# BRD9057A_SiWx917M_4-Layer_ExtSw_REF_DES_.net
KiCad netlist of a schematic drawn in Altium Designer
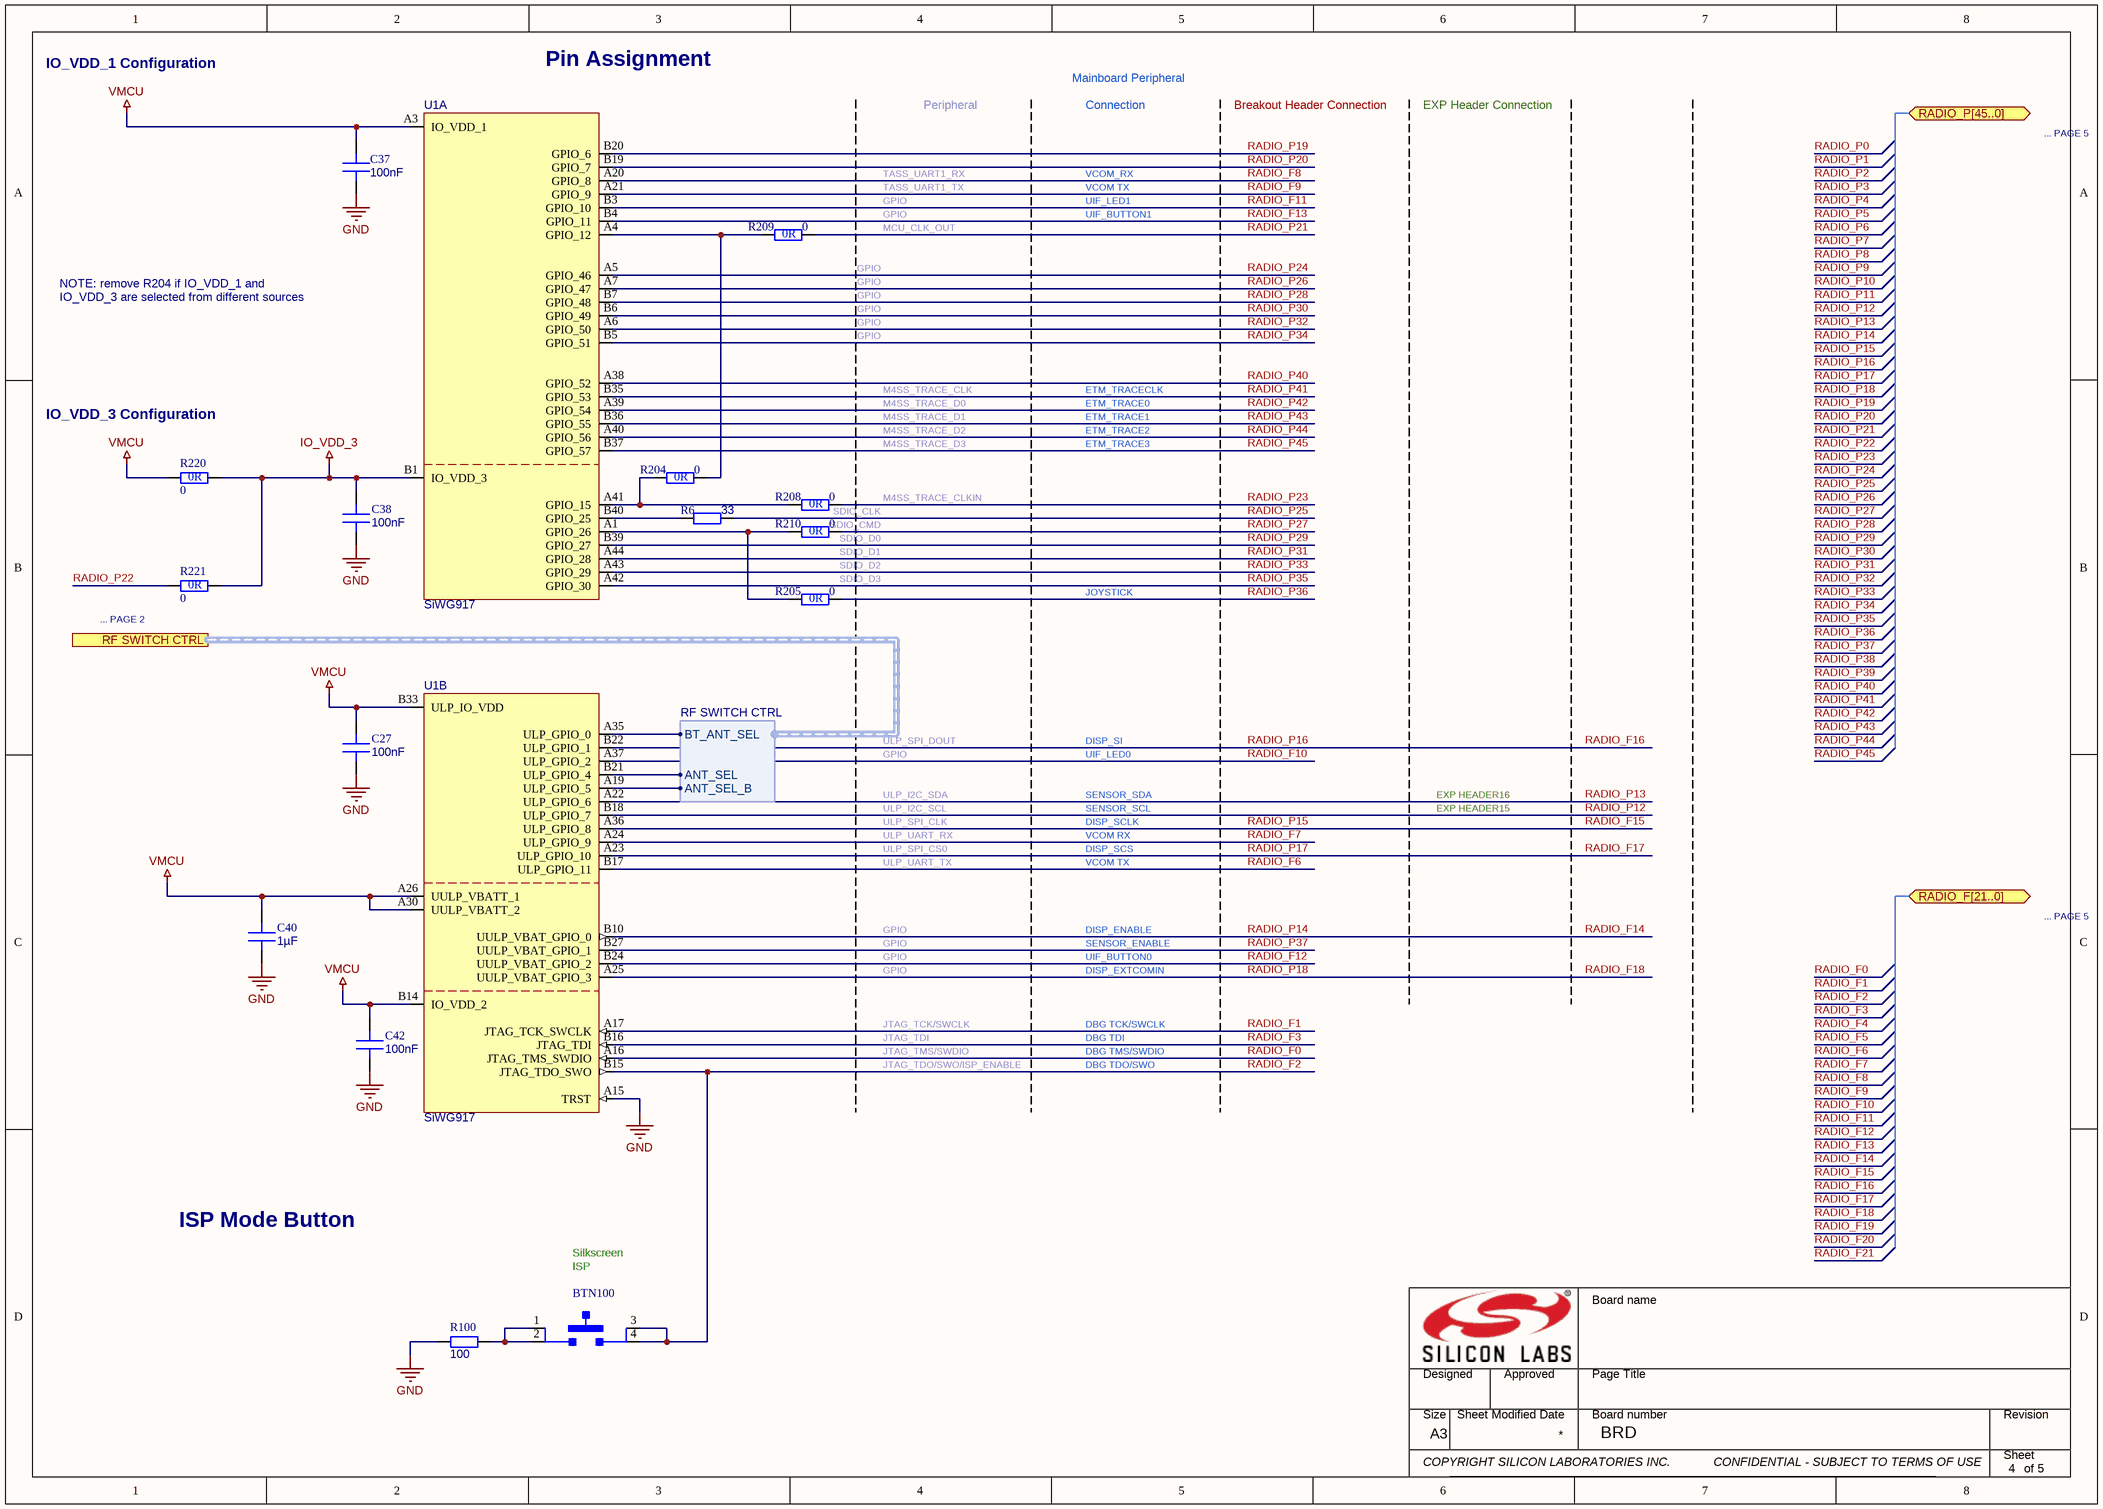
[diagram p0: BRD9057A_SiWx917M_4-Layer_ExtSw_REF_DES_A01_Page_4.SchDoc]

(export (version "E")
  (design (tool "Eeschema 10.0.6"))
  (components
    (comp (ref "BTN100")
      (value "PTS810 SJM 250 SMTR LFS")
      (footprint "SW_PTS810SJM250SMTRLFS")
      (description "Tactile Switch SPST-NO 0.05A 16V")
      (fields (field (name "MANUFACTURER") "C&K"))
      (libsource (lib "SiLabs Production Server") (part "SW_TACTILE_SPST_4PIN"))
    )
    (comp (ref "C27")
      (value "100nF")
      (footprint "C0201_GM")
      (description "CAP CER 0201 X5R 100nF 16V 10%")
      (fields (field (name "TOLERANCE") "10%"))
      (libsource (lib "SiLabs Production Server") (part "Capacitor"))
    )
    (comp (ref "C37")
      (value "100nF")
      (footprint "C0201_GM")
      (description "CAP CER 0201 X5R 100nF 16V 10%")
      (fields (field (name "TOLERANCE") "10%"))
      (libsource (lib "SiLabs Production Server") (part "Capacitor"))
    )
    (comp (ref "C38")
      (value "100nF")
      (footprint "C0201_GM")
      (description "CAP CER 0201 X5R 100nF 16V 10%")
      (fields (field (name "TOLERANCE") "10%"))
      (libsource (lib "SiLabs Production Server") (part "Capacitor"))
    )
    (comp (ref "C40")
      (value "1µF")
      (footprint "C0201_GM")
      (description "CAP CER 0201 X5R 1uF 16V 20%")
      (fields (field (name "TOLERANCE") "20%"))
      (libsource (lib "SiLabs Production Server") (part "Capacitor"))
    )
    (comp (ref "C42")
      (value "100nF")
      (footprint "C0201_GM")
      (description "CAP CER 0201 X5R 100nF 16V 10%")
      (fields (field (name "TOLERANCE") "10%"))
      (libsource (lib "SiLabs Production Server") (part "Capacitor"))
    )
    (comp (ref "R6")
      (value "33")
      (footprint "R0201")
      (description "RES 0201 33R 1/20W 1% 200ppm")
      (fields (field (name "TOLERANCE") "1%"))
      (libsource (lib "SiLabs Production Server") (part "Resistor"))
    )
    (comp (ref "R100")
      (value "100")
      (footprint "R0201")
      (description "RES 0201 100R 1/20W 1% 200ppm")
      (fields (field (name "TOLERANCE") "1%"))
      (libsource (lib "SiLabs Production Server") (part "Resistor"))
    )
    (comp (ref "R204")
      (value "0")
      (footprint "R0402")
      (description "RES 0402 0R")
      (fields (field (name "TOLERANCE") "0%"))
      (libsource (lib "SiLabs Production Server") (part "Resistor-Jumper"))
    )
    (comp (ref "R205")
      (value "0")
      (footprint "R0402")
      (description "RES 0402 0R")
      (fields (field (name "TOLERANCE") "0%"))
      (libsource (lib "SiLabs Production Server") (part "Resistor-Jumper"))
    )
    (comp (ref "R208")
      (value "0")
      (footprint "R0402")
      (description "RES 0402 0R")
      (fields (field (name "TOLERANCE") "0%"))
      (libsource (lib "SiLabs Production Server") (part "Resistor-Jumper"))
    )
    (comp (ref "R209")
      (value "0")
      (footprint "R0402")
      (description "RES 0402 0R")
      (fields (field (name "TOLERANCE") "0%"))
      (libsource (lib "SiLabs Production Server") (part "Resistor-Jumper"))
    )
    (comp (ref "R210")
      (value "0")
      (footprint "R0402")
      (description "RES 0402 0R")
      (fields (field (name "TOLERANCE") "0%"))
      (libsource (lib "SiLabs Production Server") (part "Resistor-Jumper"))
    )
    (comp (ref "R220")
      (value "0")
      (footprint "R0402")
      (description "RES 0402 0R")
      (fields (field (name "TOLERANCE") "0%"))
      (libsource (lib "SiLabs Production Server") (part "Resistor-Jumper"))
    )
    (comp (ref "R221")
      (value "0")
      (footprint "R0402")
      (description "RES 0402 0R")
      (fields (field (name "TOLERANCE") "0%"))
      (libsource (lib "SiLabs Production Server") (part "Resistor-Jumper"))
    )
    (comp (ref "U1")
      (value "SiWG917")
      (footprint "QFN84_SI_SiWx917_A1")
      (description "IC SoC 32BIT 8MB FLASH QFN84 2.4GHz Single Band Wi-Fi")
      (fields (field (name "MANUFACTURER") "Silicon Labs") (field (name "VOLTAGE") "3.63V"))
      (libsource (lib "SiLabs Production Server") (part "SiWx917"))
    )
  )
  (nets
    (net (code "4") (name "/ANT_SEL") (class "Default")
      (node (ref "U1") (pin "B21") (pinfunction "ULP_GPIO_4_B21") (pintype "bidirectional"))
    )
    (net (code "5") (name "/ANT_SEL_B") (class "Default")
      (node (ref "U1") (pin "A19") (pinfunction "ULP_GPIO_5_A19") (pintype "bidirectional"))
    )
    (net (code "6") (name "/BT_ANT_SEL") (class "Default")
      (node (ref "U1") (pin "A35") (pinfunction "ULP_GPIO_0_A35") (pintype "bidirectional"))
    )
    (net (code "7") (name "/RADIO_F0") (class "Default")
      (node (ref "U1") (pin "A16") (pinfunction "JTAG_TMS_SWDIO_A16") (pintype "input"))
    )
    (net (code "8") (name "/RADIO_F1") (class "Default")
      (node (ref "U1") (pin "A17") (pinfunction "JTAG_TCK_SWCLK_A17") (pintype "input"))
    )
    (net (code "9") (name "/RADIO_F2") (class "Default")
      (node (ref "BTN100") (pin "3") (pinfunction "3_3") (pintype "passive"))
      (node (ref "BTN100") (pin "4") (pinfunction "4_4") (pintype "passive"))
      (node (ref "U1") (pin "B15") (pinfunction "JTAG_TDO_SWO_B15") (pintype "output"))
    )
    (net (code "10") (name "/RADIO_F3") (class "Default")
      (node (ref "U1") (pin "B16") (pinfunction "JTAG_TDI_B16") (pintype "input"))
    )
    (net (code "13") (name "/RADIO_F6") (class "Default")
      (node (ref "U1") (pin "B17") (pinfunction "ULP_GPIO_11_B17") (pintype "bidirectional"))
    )
    (net (code "14") (name "/RADIO_F7") (class "Default")
      (node (ref "U1") (pin "A24") (pinfunction "ULP_GPIO_9_A24") (pintype "bidirectional"))
    )
    (net (code "15") (name "/RADIO_F8") (class "Default")
      (node (ref "U1") (pin "A20") (pinfunction "GPIO_8_A20") (pintype "bidirectional"))
    )
    (net (code "16") (name "/RADIO_F9") (class "Default")
      (node (ref "U1") (pin "A21") (pinfunction "GPIO_9_A21") (pintype "bidirectional"))
    )
    (net (code "17") (name "/RADIO_F10") (class "Default")
      (node (ref "U1") (pin "A37") (pinfunction "ULP_GPIO_2_A37") (pintype "bidirectional"))
    )
    (net (code "18") (name "/RADIO_F11") (class "Default")
      (node (ref "U1") (pin "B3") (pinfunction "GPIO_10_B3") (pintype "bidirectional"))
    )
    (net (code "19") (name "/RADIO_F12") (class "Default")
      (node (ref "U1") (pin "B24") (pinfunction "UULP_VBAT_GPIO_2_B24") (pintype "bidirectional"))
    )
    (net (code "20") (name "/RADIO_F13") (class "Default")
      (node (ref "U1") (pin "B4") (pinfunction "GPIO_11_B4") (pintype "bidirectional"))
    )
    (net (code "37") (name "/RADIO_P12") (class "Default")
      (node (ref "U1") (pin "B18") (pinfunction "ULP_GPIO_7_B18") (pintype "bidirectional"))
    )
    (net (code "38") (name "/RADIO_P13") (class "Default")
      (node (ref "U1") (pin "A22") (pinfunction "ULP_GPIO_6_A22") (pintype "bidirectional"))
    )
    (net (code "39") (name "/RADIO_P14") (class "Default")
      (node (ref "U1") (pin "B10") (pinfunction "UULP_VBAT_GPIO_0_B10") (pintype "output"))
    )
    (net (code "40") (name "/RADIO_P15") (class "Default")
      (node (ref "U1") (pin "A36") (pinfunction "ULP_GPIO_8_A36") (pintype "bidirectional"))
    )
    (net (code "41") (name "/RADIO_P16") (class "Default")
      (node (ref "U1") (pin "B22") (pinfunction "ULP_GPIO_1_B22") (pintype "bidirectional"))
    )
    (net (code "42") (name "/RADIO_P17") (class "Default")
      (node (ref "U1") (pin "A23") (pinfunction "ULP_GPIO_10_A23") (pintype "bidirectional"))
    )
    (net (code "43") (name "/RADIO_P18") (class "Default")
      (node (ref "U1") (pin "A25") (pinfunction "UULP_VBAT_GPIO_3_A25") (pintype "bidirectional"))
    )
    (net (code "44") (name "/RADIO_P19") (class "Default")
      (node (ref "U1") (pin "B20") (pinfunction "GPIO_6_B20") (pintype "bidirectional"))
    )
    (net (code "45") (name "/RADIO_P20") (class "Default")
      (node (ref "U1") (pin "B19") (pinfunction "GPIO_7_B19") (pintype "bidirectional"))
    )
    (net (code "46") (name "/RADIO_P21") (class "Default")
      (node (ref "R209") (pin "2") (pinfunction "2_2") (pintype "passive"))
    )
    (net (code "47") (name "/RADIO_P22") (class "Default")
      (node (ref "R221") (pin "1") (pinfunction "1_1") (pintype "passive"))
    )
    (net (code "48") (name "/RADIO_P23") (class "Default")
      (node (ref "R208") (pin "2") (pinfunction "2_2") (pintype "passive"))
    )
    (net (code "49") (name "/RADIO_P24") (class "Default")
      (node (ref "U1") (pin "A5") (pinfunction "GPIO_46_A5") (pintype "bidirectional"))
    )
    (net (code "50") (name "/RADIO_P25") (class "Default")
      (node (ref "R6") (pin "2") (pinfunction "2_2") (pintype "passive"))
    )
    (net (code "51") (name "/RADIO_P26") (class "Default")
      (node (ref "U1") (pin "A7") (pinfunction "GPIO_47_A7") (pintype "bidirectional"))
    )
    (net (code "52") (name "/RADIO_P27") (class "Default")
      (node (ref "R210") (pin "2") (pinfunction "2_2") (pintype "passive"))
    )
    (net (code "53") (name "/RADIO_P28") (class "Default")
      (node (ref "U1") (pin "B7") (pinfunction "GPIO_48_B7") (pintype "bidirectional"))
    )
    (net (code "54") (name "/RADIO_P29") (class "Default")
      (node (ref "U1") (pin "B39") (pinfunction "GPIO_27_B39") (pintype "bidirectional"))
    )
    (net (code "55") (name "/RADIO_P30") (class "Default")
      (node (ref "U1") (pin "B6") (pinfunction "GPIO_49_B6") (pintype "bidirectional"))
    )
    (net (code "56") (name "/RADIO_P31") (class "Default")
      (node (ref "U1") (pin "A44") (pinfunction "GPIO_28_A44") (pintype "bidirectional"))
    )
    (net (code "57") (name "/RADIO_P32") (class "Default")
      (node (ref "U1") (pin "A6") (pinfunction "GPIO_50_A6") (pintype "bidirectional"))
    )
    (net (code "58") (name "/RADIO_P33") (class "Default")
      (node (ref "U1") (pin "A43") (pinfunction "GPIO_29_A43") (pintype "bidirectional"))
    )
    (net (code "59") (name "/RADIO_P34") (class "Default")
      (node (ref "U1") (pin "B5") (pinfunction "GPIO_51_B5") (pintype "bidirectional"))
    )
    (net (code "60") (name "/RADIO_P35") (class "Default")
      (node (ref "U1") (pin "A42") (pinfunction "GPIO_30_A42") (pintype "bidirectional"))
    )
    (net (code "61") (name "/RADIO_P36") (class "Default")
      (node (ref "R205") (pin "2") (pinfunction "2_2") (pintype "passive"))
    )
    (net (code "62") (name "/RADIO_P37") (class "Default")
      (node (ref "U1") (pin "B27") (pinfunction "UULP_VBAT_GPIO_1_B27") (pintype "bidirectional"))
    )
    (net (code "65") (name "/RADIO_P40") (class "Default")
      (node (ref "U1") (pin "A38") (pinfunction "GPIO_52_A38") (pintype "bidirectional"))
    )
    (net (code "66") (name "/RADIO_P41") (class "Default")
      (node (ref "U1") (pin "B35") (pinfunction "GPIO_53_B35") (pintype "bidirectional"))
    )
    (net (code "67") (name "/RADIO_P42") (class "Default")
      (node (ref "U1") (pin "A39") (pinfunction "GPIO_54_A39") (pintype "bidirectional"))
    )
    (net (code "68") (name "/RADIO_P43") (class "Default")
      (node (ref "U1") (pin "B36") (pinfunction "GPIO_55_B36") (pintype "bidirectional"))
    )
    (net (code "69") (name "/RADIO_P44") (class "Default")
      (node (ref "U1") (pin "A40") (pinfunction "GPIO_56_A40") (pintype "bidirectional"))
    )
    (net (code "70") (name "/RADIO_P45") (class "Default")
      (node (ref "U1") (pin "B37") (pinfunction "GPIO_57_B37") (pintype "bidirectional"))
    )
    (net (code "73") (name "GND") (class "Default")
      (node (ref "C27") (pin "1") (pinfunction "1_1") (pintype "passive"))
      (node (ref "C37") (pin "1") (pinfunction "1_1") (pintype "passive"))
      (node (ref "C38") (pin "1") (pinfunction "1_1") (pintype "passive"))
      (node (ref "C40") (pin "1") (pinfunction "1_1") (pintype "passive"))
      (node (ref "C42") (pin "1") (pinfunction "1_1") (pintype "passive"))
      (node (ref "R100") (pin "2") (pinfunction "2_2") (pintype "passive"))
      (node (ref "U1") (pin "A15") (pinfunction "TRST_A15") (pintype "input"))
    )
    (net (code "74") (name "IO_VDD_3") (class "Default")
      (node (ref "C38") (pin "2") (pinfunction "2_2") (pintype "passive"))
      (node (ref "R220") (pin "2") (pinfunction "2_2") (pintype "passive"))
      (node (ref "R221") (pin "2") (pinfunction "2_2") (pintype "passive"))
      (node (ref "U1") (pin "B1") (pinfunction "IO_VDD_3_B1") (pintype "power_in"))
    )
    (net (code "75") (name "Net-(BTN100-Pad1)") (class "Default")
      (node (ref "BTN100") (pin "1") (pinfunction "1_1") (pintype "passive"))
      (node (ref "BTN100") (pin "2") (pinfunction "2_2") (pintype "passive"))
      (node (ref "R100") (pin "1") (pinfunction "1_1") (pintype "passive"))
    )
    (net (code "76") (name "Net-(U1A-GPIO_12)") (class "Default")
      (node (ref "R204") (pin "2") (pinfunction "2_2") (pintype "passive"))
      (node (ref "R209") (pin "1") (pinfunction "1_1") (pintype "passive"))
      (node (ref "U1") (pin "A4") (pinfunction "GPIO_12_A4") (pintype "bidirectional"))
    )
    (net (code "77") (name "Net-(U1A-GPIO_15)") (class "Default")
      (node (ref "R204") (pin "1") (pinfunction "1_1") (pintype "passive"))
      (node (ref "R208") (pin "1") (pinfunction "1_1") (pintype "passive"))
      (node (ref "U1") (pin "A41") (pinfunction "GPIO_15_A41") (pintype "bidirectional"))
    )
    (net (code "78") (name "Net-(U1A-GPIO_25)") (class "Default")
      (node (ref "R6") (pin "1") (pinfunction "1_1") (pintype "passive"))
      (node (ref "U1") (pin "B40") (pinfunction "GPIO_25_B40") (pintype "bidirectional"))
    )
    (net (code "79") (name "Net-(U1A-GPIO_26)") (class "Default")
      (node (ref "R205") (pin "1") (pinfunction "1_1") (pintype "passive"))
      (node (ref "R210") (pin "1") (pinfunction "1_1") (pintype "passive"))
      (node (ref "U1") (pin "A1") (pinfunction "GPIO_26_A1") (pintype "bidirectional"))
    )
    (net (code "80") (name "VMCU") (class "Default")
      (node (ref "C27") (pin "2") (pinfunction "2_2") (pintype "passive"))
      (node (ref "C37") (pin "2") (pinfunction "2_2") (pintype "passive"))
      (node (ref "C40") (pin "2") (pinfunction "2_2") (pintype "passive"))
      (node (ref "C42") (pin "2") (pinfunction "2_2") (pintype "passive"))
      (node (ref "R220") (pin "1") (pinfunction "1_1") (pintype "passive"))
      (node (ref "U1") (pin "A26") (pinfunction "UULP_VBATT_1_A26") (pintype "power_in"))
      (node (ref "U1") (pin "A3") (pinfunction "IO_VDD_1_A3") (pintype "power_in"))
      (node (ref "U1") (pin "A30") (pinfunction "UULP_VBATT_2_A30") (pintype "power_in"))
      (node (ref "U1") (pin "B14") (pinfunction "IO_VDD_2_B14") (pintype "power_in"))
      (node (ref "U1") (pin "B33") (pinfunction "ULP_IO_VDD_B33") (pintype "power_in"))
    )
  )
)
